# open-circuit.net
KiCad netlist of a schematic drawn in EAGLE
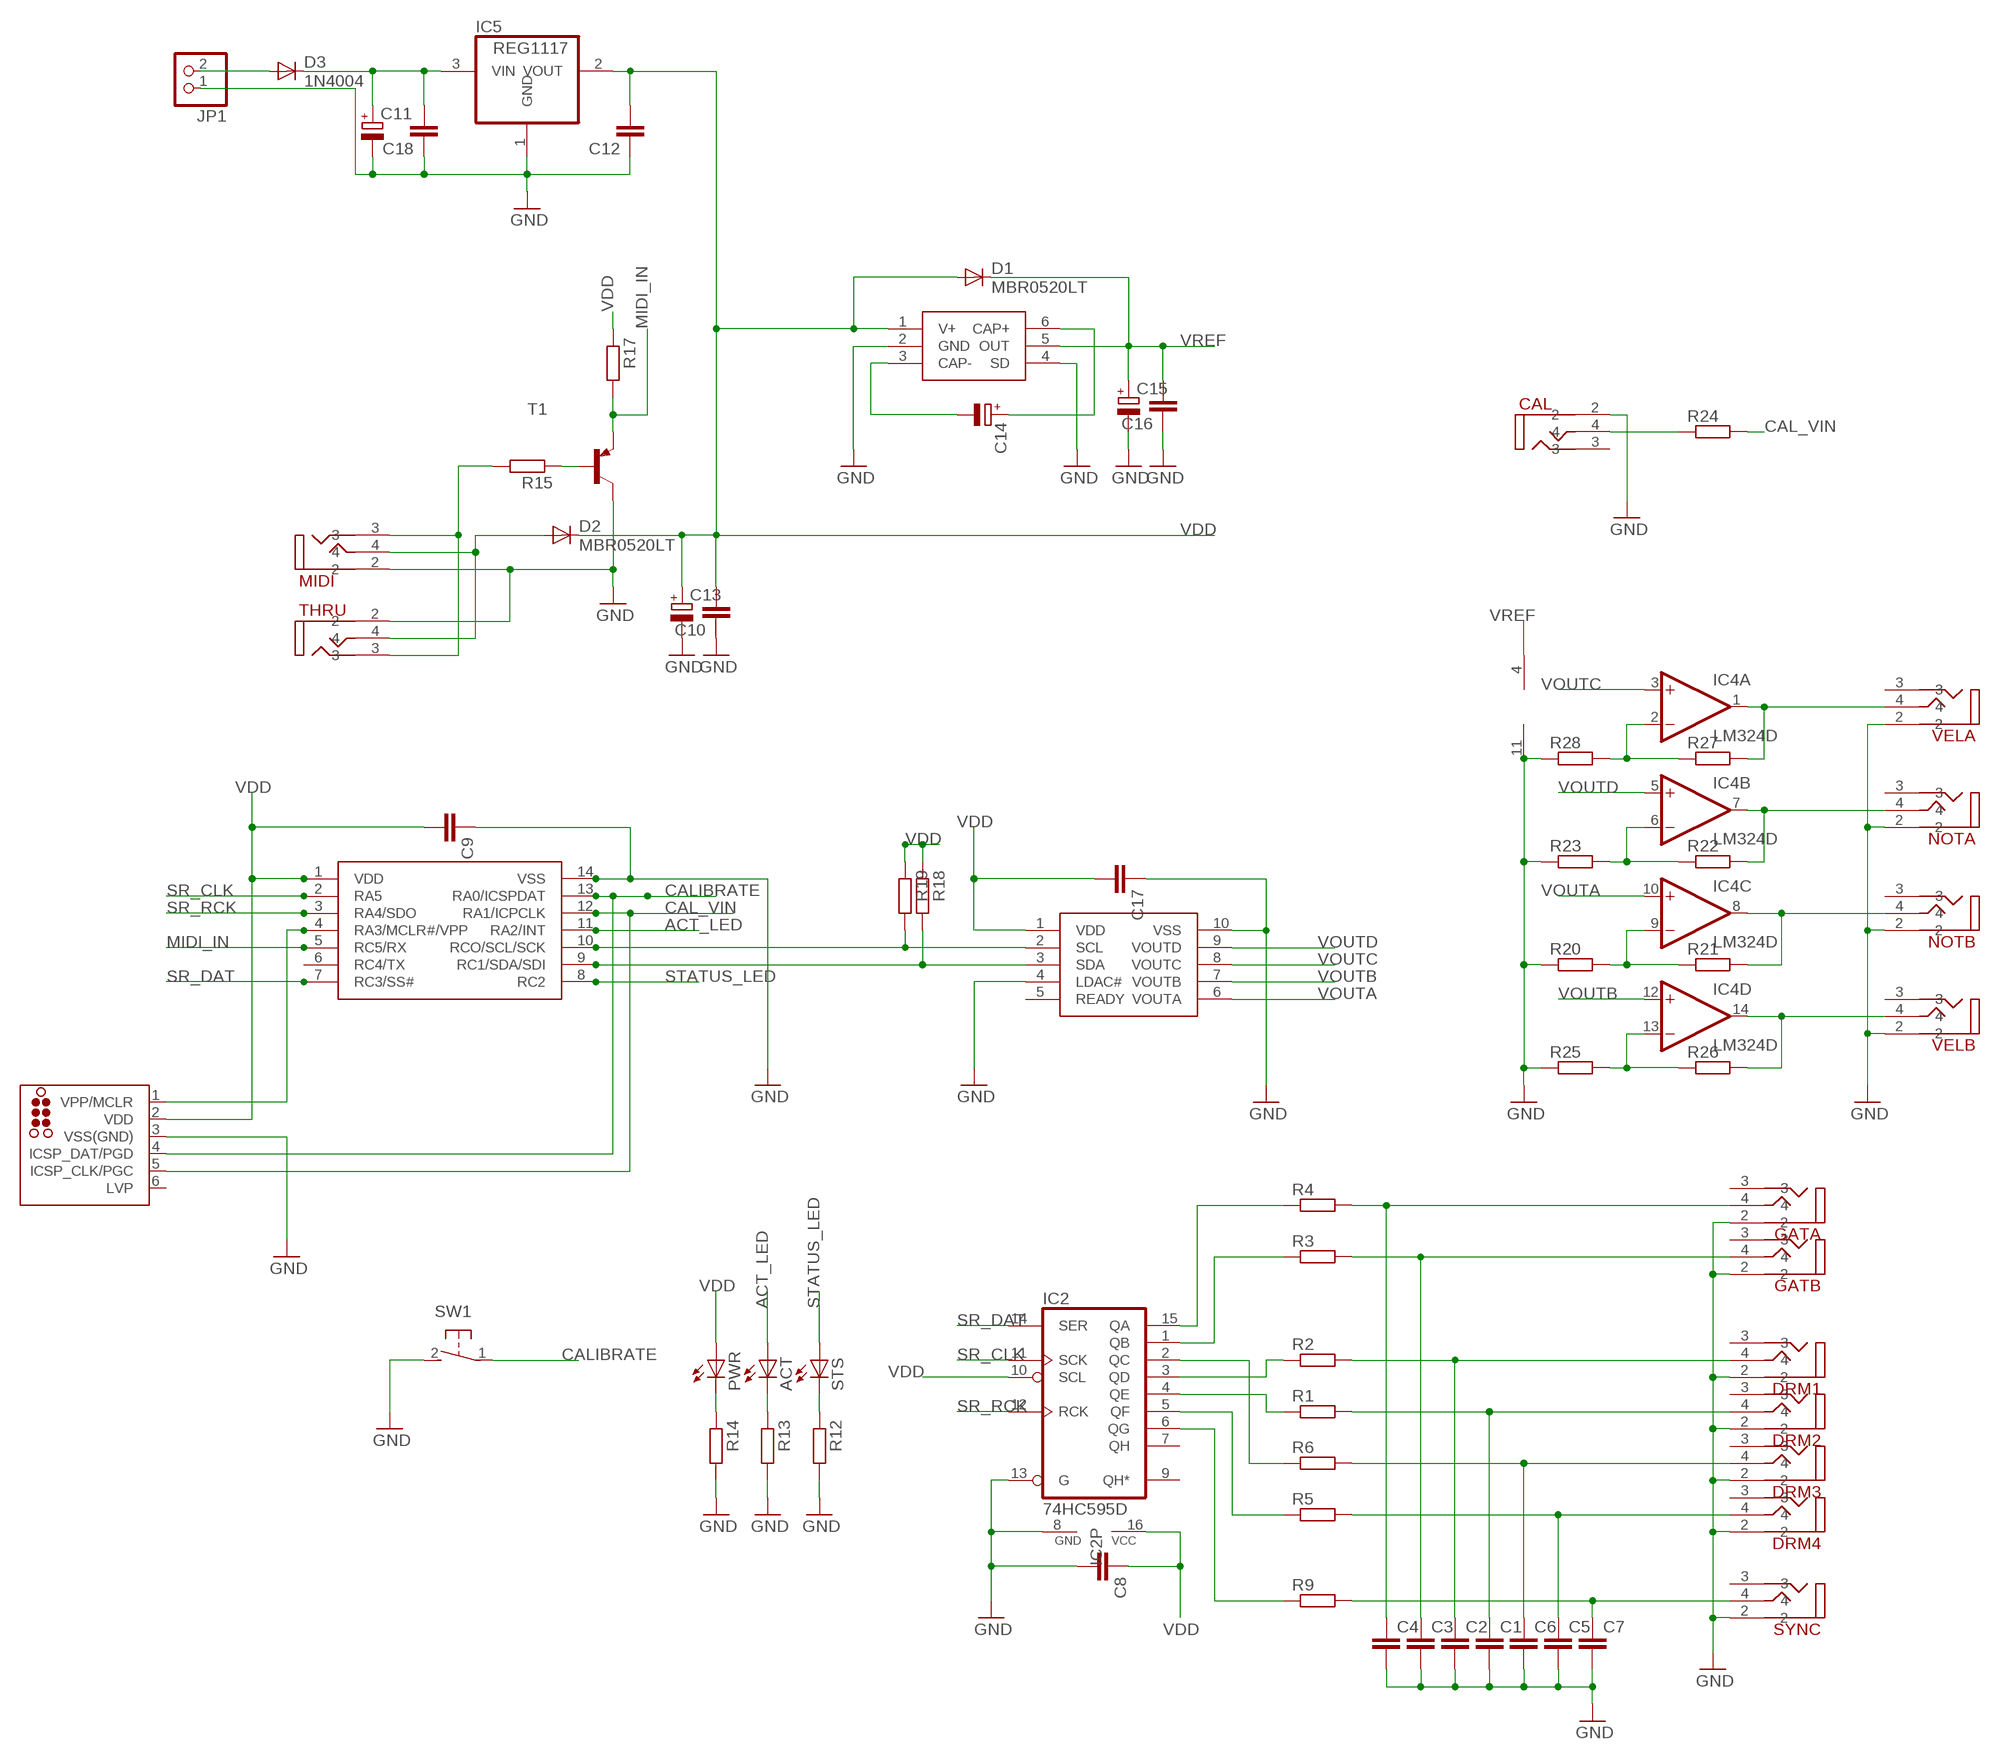
[diagram p0: schematic, sheet 1]

(export (version "E")
  (design (tool "Eeschema 10.0.6"))
  (components
    (comp (ref "ACT")
      (value "LED3MM")
      (footprint "eagle-import:LED3MM")
      (libsource (lib "eagle-import") (part "LED3MM"))
    )
    (comp (ref "C1")
      (value "C-EUC0805")
      (footprint "eagle-import:C0805")
      (libsource (lib "eagle-import") (part "C-EUC0805"))
    )
    (comp (ref "C2")
      (value "C-EUC0805")
      (footprint "eagle-import:C0805")
      (libsource (lib "eagle-import") (part "C-EUC0805"))
    )
    (comp (ref "C3")
      (value "C-EUC0805")
      (footprint "eagle-import:C0805")
      (libsource (lib "eagle-import") (part "C-EUC0805"))
    )
    (comp (ref "C4")
      (value "C-EUC0805")
      (footprint "eagle-import:C0805")
      (libsource (lib "eagle-import") (part "C-EUC0805"))
    )
    (comp (ref "C5")
      (value "C-EUC0805")
      (footprint "eagle-import:C0805")
      (libsource (lib "eagle-import") (part "C-EUC0805"))
    )
    (comp (ref "C6")
      (value "C-EUC0805")
      (footprint "eagle-import:C0805")
      (libsource (lib "eagle-import") (part "C-EUC0805"))
    )
    (comp (ref "C7")
      (value "C-EUC0805")
      (footprint "eagle-import:C0805")
      (libsource (lib "eagle-import") (part "C-EUC0805"))
    )
    (comp (ref "C8")
      (value "C-EUC0805")
      (footprint "eagle-import:C0805")
      (libsource (lib "eagle-import") (part "C-EUC0805"))
    )
    (comp (ref "C9")
      (value "C-EUC0805")
      (footprint "eagle-import:C0805")
      (libsource (lib "eagle-import") (part "C-EUC0805"))
    )
    (comp (ref "C10")
      (value "C-EUC0805")
      (footprint "eagle-import:C0805")
      (libsource (lib "eagle-import") (part "C-EUC0805"))
    )
    (comp (ref "C11")
      (value "CPOL-EUE2.5-5")
      (footprint "eagle-import:E2,5-5")
      (libsource (lib "eagle-import") (part "resistor_CPOL-EUE2.5-5"))
    )
    (comp (ref "C12")
      (value "C-EUC0805")
      (footprint "eagle-import:C0805")
      (libsource (lib "eagle-import") (part "C-EUC0805"))
    )
    (comp (ref "C13")
      (value "CPOL-EUSMCA")
      (footprint "eagle-import:SMC_A")
      (libsource (lib "eagle-import") (part "CPOL-EUSMCA"))
    )
    (comp (ref "C14")
      (value "CPOL-EUSMCA")
      (footprint "eagle-import:SMC_A")
      (libsource (lib "eagle-import") (part "CPOL-EUSMCA"))
    )
    (comp (ref "C15")
      (value "CPOL-EUSMCA")
      (footprint "eagle-import:SMC_A")
      (libsource (lib "eagle-import") (part "CPOL-EUSMCA"))
    )
    (comp (ref "C16")
      (value "C-EUC0805")
      (footprint "eagle-import:C0805")
      (libsource (lib "eagle-import") (part "C-EUC0805"))
    )
    (comp (ref "C17")
      (value "C-EUC0805")
      (footprint "eagle-import:C0805")
      (libsource (lib "eagle-import") (part "C-EUC0805"))
    )
    (comp (ref "C18")
      (value "C-EUC0805")
      (footprint "eagle-import:C0805")
      (libsource (lib "eagle-import") (part "C-EUC0805"))
    )
    (comp (ref "CAL")
      (value "VERTICAL_3_5MM_SOCKET")
      (footprint "eagle-import:VERTICAL_3_5MM_SOCKET")
      (libsource (lib "eagle-import") (part "VERTICAL_3_5MM_SOCKET"))
    )
    (comp (ref "D1")
      (value "MBR0520LT")
      (footprint "eagle-import:SOD123")
      (libsource (lib "eagle-import") (part "MBR0520LT"))
    )
    (comp (ref "D2")
      (value "MBR0520LT")
      (footprint "eagle-import:SOD123")
      (libsource (lib "eagle-import") (part "MBR0520LT"))
    )
    (comp (ref "D3")
      (value "1N4004")
      (footprint "eagle-import:DO-VERT")
      (libsource (lib "eagle-import") (part "1N4004"))
    )
    (comp (ref "DRM1")
      (value "VERTICAL_3_5MM_SOCKET")
      (footprint "eagle-import:VERTICAL_3_5MM_SOCKET")
      (libsource (lib "eagle-import") (part "VERTICAL_3_5MM_SOCKET"))
    )
    (comp (ref "DRM2")
      (value "VERTICAL_3_5MM_SOCKET")
      (footprint "eagle-import:VERTICAL_3_5MM_SOCKET")
      (libsource (lib "eagle-import") (part "VERTICAL_3_5MM_SOCKET"))
    )
    (comp (ref "DRM3")
      (value "VERTICAL_3_5MM_SOCKET")
      (footprint "eagle-import:VERTICAL_3_5MM_SOCKET")
      (libsource (lib "eagle-import") (part "VERTICAL_3_5MM_SOCKET"))
    )
    (comp (ref "DRM4")
      (value "VERTICAL_3_5MM_SOCKET")
      (footprint "eagle-import:VERTICAL_3_5MM_SOCKET")
      (libsource (lib "eagle-import") (part "VERTICAL_3_5MM_SOCKET"))
    )
    (comp (ref "GATA")
      (value "VERTICAL_3_5MM_SOCKET")
      (footprint "eagle-import:VERTICAL_3_5MM_SOCKET")
      (libsource (lib "eagle-import") (part "VERTICAL_3_5MM_SOCKET"))
    )
    (comp (ref "GATB")
      (value "VERTICAL_3_5MM_SOCKET")
      (footprint "eagle-import:VERTICAL_3_5MM_SOCKET")
      (libsource (lib "eagle-import") (part "VERTICAL_3_5MM_SOCKET"))
    )
    (comp (ref "IC1")
      (value "PIC16F1825SO14")
      (footprint "eagle-import:SO14")
      (libsource (lib "eagle-import") (part "PIC16F1825SO14"))
    )
    (comp (ref "IC2")
      (value "74HC595D")
      (footprint "eagle-import:SO16")
      (libsource (lib "eagle-import") (part "74595DHC"))
    )
    (comp (ref "IC3")
      (value "MCP4728_QUAD_DAC")
      (footprint "eagle-import:MSOP10")
      (libsource (lib "eagle-import") (part "MCP4728_QUAD_DAC"))
    )
    (comp (ref "IC4")
      (value "LM324D")
      (footprint "eagle-import:SO14")
      (libsource (lib "eagle-import") (part "LM324D"))
    )
    (comp (ref "IC5")
      (value "REG1117")
      (footprint "eagle-import:SOT223")
      (libsource (lib "eagle-import") (part "REG1117"))
    )
    (comp (ref "IC6")
      (value "LM27675M5_CHARGEPUMP")
      (footprint "eagle-import:SOT23-6")
      (libsource (lib "eagle-import") (part "LM27675M5_CHARGEPUMP"))
    )
    (comp (ref "ISCP")
      (value "TC2030-MCP-NL")
      (footprint "eagle-import:TC2030-MCP-NL")
      (libsource (lib "eagle-import") (part "TC2030-MCP-NL"))
    )
    (comp (ref "JP1")
      (value "PINHD-1X2")
      (footprint "eagle-import:1X02")
      (libsource (lib "eagle-import") (part "PINHD-1X2"))
    )
    (comp (ref "MIDI")
      (value "VERTICAL_3_5MM_SOCKET")
      (footprint "eagle-import:VERTICAL_3_5MM_SOCKET")
      (libsource (lib "eagle-import") (part "VERTICAL_3_5MM_SOCKET"))
    )
    (comp (ref "NOTA")
      (value "VERTICAL_3_5MM_SOCKET")
      (footprint "eagle-import:VERTICAL_3_5MM_SOCKET")
      (libsource (lib "eagle-import") (part "VERTICAL_3_5MM_SOCKET"))
    )
    (comp (ref "NOTB")
      (value "VERTICAL_3_5MM_SOCKET")
      (footprint "eagle-import:VERTICAL_3_5MM_SOCKET")
      (libsource (lib "eagle-import") (part "VERTICAL_3_5MM_SOCKET"))
    )
    (comp (ref "PWR")
      (value "LED3MM")
      (footprint "eagle-import:LED3MM")
      (libsource (lib "eagle-import") (part "LED3MM"))
    )
    (comp (ref "R1")
      (value "R-EU_R0805")
      (footprint "eagle-import:R0805")
      (libsource (lib "eagle-import") (part "R-EU_R0805"))
    )
    (comp (ref "R2")
      (value "R-EU_R0805")
      (footprint "eagle-import:R0805")
      (libsource (lib "eagle-import") (part "R-EU_R0805"))
    )
    (comp (ref "R3")
      (value "R-EU_R0805")
      (footprint "eagle-import:R0805")
      (libsource (lib "eagle-import") (part "R-EU_R0805"))
    )
    (comp (ref "R4")
      (value "R-EU_R0805")
      (footprint "eagle-import:R0805")
      (libsource (lib "eagle-import") (part "R-EU_R0805"))
    )
    (comp (ref "R5")
      (value "R-EU_R0805")
      (footprint "eagle-import:R0805")
      (libsource (lib "eagle-import") (part "R-EU_R0805"))
    )
    (comp (ref "R6")
      (value "R-EU_R0805")
      (footprint "eagle-import:R0805")
      (libsource (lib "eagle-import") (part "R-EU_R0805"))
    )
    (comp (ref "R9")
      (value "R-EU_R0805")
      (footprint "eagle-import:R0805")
      (libsource (lib "eagle-import") (part "R-EU_R0805"))
    )
    (comp (ref "R12")
      (value "R-EU_R0805")
      (footprint "eagle-import:R0805")
      (libsource (lib "eagle-import") (part "R-EU_R0805"))
    )
    (comp (ref "R13")
      (value "R-EU_R0805")
      (footprint "eagle-import:R0805")
      (libsource (lib "eagle-import") (part "R-EU_R0805"))
    )
    (comp (ref "R14")
      (value "R-EU_R0805")
      (footprint "eagle-import:R0805")
      (libsource (lib "eagle-import") (part "R-EU_R0805"))
    )
    (comp (ref "R15")
      (value "R-EU_R0805")
      (footprint "eagle-import:R0805")
      (libsource (lib "eagle-import") (part "R-EU_R0805"))
    )
    (comp (ref "R17")
      (value "R-EU_R0805")
      (footprint "eagle-import:R0805")
      (libsource (lib "eagle-import") (part "R-EU_R0805"))
    )
    (comp (ref "R18")
      (value "R-EU_R0805")
      (footprint "eagle-import:R0805")
      (libsource (lib "eagle-import") (part "R-EU_R0805"))
    )
    (comp (ref "R19")
      (value "R-EU_R0805")
      (footprint "eagle-import:R0805")
      (libsource (lib "eagle-import") (part "R-EU_R0805"))
    )
    (comp (ref "R20")
      (value "R-EU_R0805")
      (footprint "eagle-import:R0805")
      (libsource (lib "eagle-import") (part "R-EU_R0805"))
    )
    (comp (ref "R21")
      (value "R-EU_R0805")
      (footprint "eagle-import:R0805")
      (libsource (lib "eagle-import") (part "R-EU_R0805"))
    )
    (comp (ref "R22")
      (value "R-EU_R0805")
      (footprint "eagle-import:R0805")
      (libsource (lib "eagle-import") (part "R-EU_R0805"))
    )
    (comp (ref "R23")
      (value "R-EU_R0805")
      (footprint "eagle-import:R0805")
      (libsource (lib "eagle-import") (part "R-EU_R0805"))
    )
    (comp (ref "R24")
      (value "R-EU_R0805")
      (footprint "eagle-import:R0805")
      (libsource (lib "eagle-import") (part "R-EU_R0805"))
    )
    (comp (ref "R25")
      (value "R-EU_R0805")
      (footprint "eagle-import:R0805")
      (libsource (lib "eagle-import") (part "R-EU_R0805"))
    )
    (comp (ref "R26")
      (value "R-EU_R0805")
      (footprint "eagle-import:R0805")
      (libsource (lib "eagle-import") (part "R-EU_R0805"))
    )
    (comp (ref "R27")
      (value "R-EU_R0805")
      (footprint "eagle-import:R0805")
      (libsource (lib "eagle-import") (part "R-EU_R0805"))
    )
    (comp (ref "R28")
      (value "R-EU_R0805")
      (footprint "eagle-import:R0805")
      (libsource (lib "eagle-import") (part "R-EU_R0805"))
    )
    (comp (ref "STS")
      (value "LED3MM")
      (footprint "eagle-import:LED3MM")
      (libsource (lib "eagle-import") (part "LED3MM"))
    )
    (comp (ref "SW1")
      (value "31-XX")
      (footprint "eagle-import:B3F-31XX")
      (fields (field (name "MPN") "B3F-3100"))
      (libsource (lib "eagle-import") (part "31-XX"))
    )
    (comp (ref "SYNC")
      (value "VERTICAL_3_5MM_SOCKET")
      (footprint "eagle-import:VERTICAL_3_5MM_SOCKET")
      (libsource (lib "eagle-import") (part "VERTICAL_3_5MM_SOCKET"))
    )
    (comp (ref "T1")
      (value "MMBT3906LT1-PNP-SOT23-BEC")
      (footprint "eagle-import:SOT23-BEC")
      (libsource (lib "eagle-import") (part "-PNP-SOT23-BECMMBT3906LT1"))
    )
    (comp (ref "THRU")
      (value "VERTICAL_3_5MM_SOCKET")
      (footprint "eagle-import:VERTICAL_3_5MM_SOCKET")
      (libsource (lib "eagle-import") (part "VERTICAL_3_5MM_SOCKET"))
    )
    (comp (ref "VELA")
      (value "VERTICAL_3_5MM_SOCKET")
      (footprint "eagle-import:VERTICAL_3_5MM_SOCKET")
      (libsource (lib "eagle-import") (part "VERTICAL_3_5MM_SOCKET"))
    )
    (comp (ref "VELB")
      (value "VERTICAL_3_5MM_SOCKET")
      (footprint "eagle-import:VERTICAL_3_5MM_SOCKET")
      (libsource (lib "eagle-import") (part "VERTICAL_3_5MM_SOCKET"))
    )
  )
  (nets
    (net (code "1") (name "/ACT_LED") (class "Default")
      (node (ref "ACT") (pin "A") (pinfunction "A_A") (pintype "passive"))
      (node (ref "IC1") (pin "11") (pinfunction "RA2/INT_11") (pintype "bidirectional"))
    )
    (net (code "2") (name "/CALIBRATE") (class "Default")
      (node (ref "IC1") (pin "13") (pinfunction "RA0/ICSPDAT_13") (pintype "bidirectional"))
      (node (ref "ISCP") (pin "4") (pinfunction "ICSP_DAT/PGD_4") (pintype "bidirectional"))
      (node (ref "SW1") (pin "1") (pinfunction "P_1") (pintype "passive"))
    )
    (net (code "3") (name "/CAL_VIN") (class "Default")
      (node (ref "IC1") (pin "12") (pinfunction "RA1/ICPCLK_12") (pintype "bidirectional"))
      (node (ref "ISCP") (pin "5") (pinfunction "ICSP_CLK/PGC_5") (pintype "output"))
      (node (ref "R24") (pin "2") (pinfunction "2_2") (pintype "passive"))
    )
    (net (code "4") (name "/MIDI_IN") (class "Default")
      (node (ref "IC1") (pin "5") (pinfunction "RC5/RX_5") (pintype "bidirectional"))
      (node (ref "R17") (pin "2") (pinfunction "2_2") (pintype "passive"))
      (node (ref "T1") (pin "E") (pinfunction "E_E") (pintype "passive"))
    )
    (net (code "5") (name "/SR_CLK") (class "Default")
      (node (ref "IC1") (pin "2") (pinfunction "RA5_2") (pintype "bidirectional"))
      (node (ref "IC2") (pin "11") (pinfunction "SCK_11") (pintype "input"))
    )
    (net (code "6") (name "/SR_DAT") (class "Default")
      (node (ref "IC1") (pin "7") (pinfunction "RC3/SS#_7") (pintype "bidirectional"))
      (node (ref "IC2") (pin "14") (pinfunction "SER_14") (pintype "input"))
    )
    (net (code "7") (name "/SR_RCK") (class "Default")
      (node (ref "IC1") (pin "3") (pinfunction "RA4/SDO_3") (pintype "bidirectional"))
      (node (ref "IC2") (pin "12") (pinfunction "RCK_12") (pintype "input"))
    )
    (net (code "8") (name "/STATUS_LED") (class "Default")
      (node (ref "IC1") (pin "8") (pinfunction "RC2_8") (pintype "bidirectional"))
      (node (ref "STS") (pin "A") (pinfunction "A_A") (pintype "passive"))
    )
    (net (code "9") (name "/VDD") (class "Default")
      (node (ref "C10") (pin "2") (pinfunction "2_2") (pintype "passive"))
      (node (ref "C12") (pin "2") (pinfunction "2_2") (pintype "passive"))
      (node (ref "C13") (pin "+") (pinfunction "+_+") (pintype "passive"))
      (node (ref "C17") (pin "2") (pinfunction "2_2") (pintype "passive"))
      (node (ref "C8") (pin "1") (pinfunction "1_1") (pintype "passive"))
      (node (ref "C9") (pin "2") (pinfunction "2_2") (pintype "passive"))
      (node (ref "D1") (pin "A") (pinfunction "A_A") (pintype "passive"))
      (node (ref "D2") (pin "C") (pinfunction "C_C") (pintype "passive"))
      (node (ref "IC1") (pin "1") (pinfunction "VDD_1") (pintype "power_in"))
      (node (ref "IC2") (pin "10") (pinfunction "SCL_10") (pintype "input"))
      (node (ref "IC2") (pin "16") (pinfunction "VCC_16") (pintype "power_in"))
      (node (ref "IC3") (pin "1") (pinfunction "VDD_1") (pintype "power_in"))
      (node (ref "IC5") (pin "2") (pinfunction "VOUT_2") (pintype "output"))
      (node (ref "IC6") (pin "1") (pinfunction "V+_1") (pintype "bidirectional"))
      (node (ref "ISCP") (pin "2") (pinfunction "VDD_2") (pintype "power_in"))
      (node (ref "PWR") (pin "A") (pinfunction "A_A") (pintype "passive"))
      (node (ref "R17") (pin "1") (pinfunction "1_1") (pintype "passive"))
      (node (ref "R18") (pin "1") (pinfunction "1_1") (pintype "passive"))
      (node (ref "R19") (pin "1") (pinfunction "1_1") (pintype "passive"))
    )
    (net (code "10") (name "/VOUTA") (class "Default")
      (node (ref "IC3") (pin "6") (pinfunction "VOUTA_6") (pintype "bidirectional"))
      (node (ref "IC4") (pin "10") (pinfunction "+IN_10") (pintype "input"))
    )
    (net (code "11") (name "/VOUTB") (class "Default")
      (node (ref "IC3") (pin "7") (pinfunction "VOUTB_7") (pintype "bidirectional"))
      (node (ref "IC4") (pin "12") (pinfunction "+IN_12") (pintype "input"))
    )
    (net (code "12") (name "/VOUTC") (class "Default")
      (node (ref "IC3") (pin "8") (pinfunction "VOUTC_8") (pintype "bidirectional"))
      (node (ref "IC4") (pin "3") (pinfunction "+IN_3") (pintype "input"))
    )
    (net (code "13") (name "/VOUTD") (class "Default")
      (node (ref "IC3") (pin "9") (pinfunction "VOUTD_9") (pintype "bidirectional"))
      (node (ref "IC4") (pin "5") (pinfunction "+IN_5") (pintype "input"))
    )
    (net (code "14") (name "/VREF") (class "Default")
      (node (ref "C15") (pin "+") (pinfunction "+_+") (pintype "passive"))
      (node (ref "C16") (pin "2") (pinfunction "2_2") (pintype "passive"))
      (node (ref "D1") (pin "C") (pinfunction "C_C") (pintype "passive"))
      (node (ref "IC4") (pin "4") (pinfunction "V+_4") (pintype "power_in"))
      (node (ref "IC6") (pin "5") (pinfunction "OUT_5") (pintype "bidirectional"))
    )
    (net (code "15") (name "GND") (class "Default")
      (node (ref "C1") (pin "2") (pinfunction "2_2") (pintype "passive"))
      (node (ref "C10") (pin "1") (pinfunction "1_1") (pintype "passive"))
      (node (ref "C11") (pin "-") (pinfunction "-_-") (pintype "passive"))
      (node (ref "C12") (pin "1") (pinfunction "1_1") (pintype "passive"))
      (node (ref "C13") (pin "-") (pinfunction "-_-") (pintype "passive"))
      (node (ref "C15") (pin "-") (pinfunction "-_-") (pintype "passive"))
      (node (ref "C16") (pin "1") (pinfunction "1_1") (pintype "passive"))
      (node (ref "C17") (pin "1") (pinfunction "1_1") (pintype "passive"))
      (node (ref "C18") (pin "1") (pinfunction "1_1") (pintype "passive"))
      (node (ref "C2") (pin "2") (pinfunction "2_2") (pintype "passive"))
      (node (ref "C3") (pin "2") (pinfunction "2_2") (pintype "passive"))
      (node (ref "C4") (pin "2") (pinfunction "2_2") (pintype "passive"))
      (node (ref "C5") (pin "2") (pinfunction "2_2") (pintype "passive"))
      (node (ref "C6") (pin "2") (pinfunction "2_2") (pintype "passive"))
      (node (ref "C7") (pin "2") (pinfunction "2_2") (pintype "passive"))
      (node (ref "C8") (pin "2") (pinfunction "2_2") (pintype "passive"))
      (node (ref "C9") (pin "1") (pinfunction "1_1") (pintype "passive"))
      (node (ref "CAL") (pin "2") (pinfunction "2_2") (pintype "bidirectional"))
      (node (ref "DRM1") (pin "2") (pinfunction "2_2") (pintype "bidirectional"))
      (node (ref "DRM2") (pin "2") (pinfunction "2_2") (pintype "bidirectional"))
      (node (ref "DRM3") (pin "2") (pinfunction "2_2") (pintype "bidirectional"))
      (node (ref "DRM4") (pin "2") (pinfunction "2_2") (pintype "bidirectional"))
      (node (ref "GATA") (pin "2") (pinfunction "2_2") (pintype "bidirectional"))
      (node (ref "GATB") (pin "2") (pinfunction "2_2") (pintype "bidirectional"))
      (node (ref "IC1") (pin "14") (pinfunction "VSS_14") (pintype "power_in"))
      (node (ref "IC2") (pin "13") (pinfunction "G_13") (pintype "input"))
      (node (ref "IC2") (pin "8") (pinfunction "GND_8") (pintype "power_in"))
      (node (ref "IC3") (pin "10") (pinfunction "VSS_10") (pintype "power_in"))
      (node (ref "IC3") (pin "4") (pinfunction "LDAC#_4") (pintype "bidirectional"))
      (node (ref "IC4") (pin "11") (pinfunction "V-_11") (pintype "power_in"))
      (node (ref "IC5") (pin "1") (pinfunction "GND_1") (pintype "power_in"))
      (node (ref "IC6") (pin "2") (pinfunction "GND_2") (pintype "bidirectional"))
      (node (ref "IC6") (pin "4") (pinfunction "SD_4") (pintype "bidirectional"))
      (node (ref "ISCP") (pin "3") (pinfunction "VSS(GND)_3") (pintype "power_in"))
      (node (ref "JP1") (pin "1") (pinfunction "1_1") (pintype "passive"))
      (node (ref "MIDI") (pin "2") (pinfunction "2_2") (pintype "bidirectional"))
      (node (ref "NOTA") (pin "2") (pinfunction "2_2") (pintype "bidirectional"))
      (node (ref "NOTB") (pin "2") (pinfunction "2_2") (pintype "bidirectional"))
      (node (ref "R12") (pin "2") (pinfunction "2_2") (pintype "passive"))
      (node (ref "R13") (pin "2") (pinfunction "2_2") (pintype "passive"))
      (node (ref "R14") (pin "2") (pinfunction "2_2") (pintype "passive"))
      (node (ref "R20") (pin "1") (pinfunction "1_1") (pintype "passive"))
      (node (ref "R23") (pin "1") (pinfunction "1_1") (pintype "passive"))
      (node (ref "R25") (pin "1") (pinfunction "1_1") (pintype "passive"))
      (node (ref "R28") (pin "1") (pinfunction "1_1") (pintype "passive"))
      (node (ref "SW1") (pin "2") (pinfunction "S_2") (pintype "passive"))
      (node (ref "SYNC") (pin "2") (pinfunction "2_2") (pintype "bidirectional"))
      (node (ref "T1") (pin "C") (pinfunction "C_C") (pintype "passive"))
      (node (ref "THRU") (pin "2") (pinfunction "2_2") (pintype "bidirectional"))
      (node (ref "VELA") (pin "2") (pinfunction "2_2") (pintype "bidirectional"))
      (node (ref "VELB") (pin "2") (pinfunction "2_2") (pintype "bidirectional"))
    )
    (net (code "16") (name "Net-(ACT-C)") (class "Default")
      (node (ref "ACT") (pin "K") (pinfunction "C_K") (pintype "passive"))
      (node (ref "R13") (pin "1") (pinfunction "1_1") (pintype "passive"))
    )
    (net (code "17") (name "Net-(C1-Pad1)") (class "Default")
      (node (ref "C1") (pin "1") (pinfunction "1_1") (pintype "passive"))
      (node (ref "DRM2") (pin "4") (pinfunction "4_4") (pintype "bidirectional"))
      (node (ref "R1") (pin "2") (pinfunction "2_2") (pintype "passive"))
    )
    (net (code "18") (name "Net-(C2-Pad1)") (class "Default")
      (node (ref "C2") (pin "1") (pinfunction "1_1") (pintype "passive"))
      (node (ref "DRM1") (pin "4") (pinfunction "4_4") (pintype "bidirectional"))
      (node (ref "R2") (pin "2") (pinfunction "2_2") (pintype "passive"))
    )
    (net (code "19") (name "Net-(C3-Pad1)") (class "Default")
      (node (ref "C3") (pin "1") (pinfunction "1_1") (pintype "passive"))
      (node (ref "GATB") (pin "4") (pinfunction "4_4") (pintype "bidirectional"))
      (node (ref "R3") (pin "2") (pinfunction "2_2") (pintype "passive"))
    )
    (net (code "20") (name "Net-(C4-Pad1)") (class "Default")
      (node (ref "C4") (pin "1") (pinfunction "1_1") (pintype "passive"))
      (node (ref "GATA") (pin "4") (pinfunction "4_4") (pintype "bidirectional"))
      (node (ref "R4") (pin "2") (pinfunction "2_2") (pintype "passive"))
    )
    (net (code "21") (name "Net-(C5-Pad1)") (class "Default")
      (node (ref "C5") (pin "1") (pinfunction "1_1") (pintype "passive"))
      (node (ref "DRM4") (pin "4") (pinfunction "4_4") (pintype "bidirectional"))
      (node (ref "R5") (pin "2") (pinfunction "2_2") (pintype "passive"))
    )
    (net (code "22") (name "Net-(C6-Pad1)") (class "Default")
      (node (ref "C6") (pin "1") (pinfunction "1_1") (pintype "passive"))
      (node (ref "DRM3") (pin "4") (pinfunction "4_4") (pintype "bidirectional"))
      (node (ref "R6") (pin "2") (pinfunction "2_2") (pintype "passive"))
    )
    (net (code "23") (name "Net-(C7-Pad1)") (class "Default")
      (node (ref "C7") (pin "1") (pinfunction "1_1") (pintype "passive"))
      (node (ref "R9") (pin "2") (pinfunction "2_2") (pintype "passive"))
      (node (ref "SYNC") (pin "4") (pinfunction "4_4") (pintype "bidirectional"))
    )
    (net (code "24") (name "Net-(CAL-Pad4)") (class "Default")
      (node (ref "CAL") (pin "4") (pinfunction "4_4") (pintype "bidirectional"))
      (node (ref "R24") (pin "1") (pinfunction "1_1") (pintype "passive"))
    )
    (net (code "25") (name "Net-(D2-PadA)") (class "Default")
      (node (ref "D2") (pin "A") (pinfunction "A_A") (pintype "passive"))
      (node (ref "MIDI") (pin "4") (pinfunction "4_4") (pintype "bidirectional"))
      (node (ref "THRU") (pin "4") (pinfunction "4_4") (pintype "bidirectional"))
    )
    (net (code "26") (name "Net-(D3-PadA)") (class "Default")
      (node (ref "D3") (pin "A") (pinfunction "A_A") (pintype "passive"))
      (node (ref "JP1") (pin "2") (pinfunction "2_2") (pintype "passive"))
    )
    (net (code "27") (name "Net-(IC1-RA3{slash}MCLR#{slash}VPP)") (class "Default")
      (node (ref "IC1") (pin "4") (pinfunction "RA3/MCLR#/VPP_4") (pintype "input"))
      (node (ref "ISCP") (pin "1") (pinfunction "VPP/MCLR_1") (pintype "passive"))
    )
    (net (code "28") (name "Net-(IC1-RC1{slash}SDA{slash}SDI)") (class "Default")
      (node (ref "IC1") (pin "9") (pinfunction "RC1/SDA/SDI_9") (pintype "bidirectional"))
      (node (ref "IC3") (pin "3") (pinfunction "SDA_3") (pintype "bidirectional"))
      (node (ref "R18") (pin "2") (pinfunction "2_2") (pintype "passive"))
    )
    (net (code "29") (name "Net-(IC1-RCO{slash}SCL{slash}SCK)") (class "Default")
      (node (ref "IC1") (pin "10") (pinfunction "RCO/SCL/SCK_10") (pintype "bidirectional"))
      (node (ref "IC3") (pin "2") (pinfunction "SCL_2") (pintype "bidirectional"))
      (node (ref "R19") (pin "2") (pinfunction "2_2") (pintype "passive"))
    )
    (net (code "30") (name "Net-(IC2A-QA)") (class "Default")
      (node (ref "IC2") (pin "15") (pinfunction "QA_15") (pintype "tri_state"))
      (node (ref "R4") (pin "1") (pinfunction "1_1") (pintype "passive"))
    )
    (net (code "31") (name "Net-(IC2A-QB)") (class "Default")
      (node (ref "IC2") (pin "1") (pinfunction "QB_1") (pintype "tri_state"))
      (node (ref "R3") (pin "1") (pinfunction "1_1") (pintype "passive"))
    )
    (net (code "32") (name "Net-(IC2A-QC)") (class "Default")
      (node (ref "IC2") (pin "2") (pinfunction "QC_2") (pintype "tri_state"))
      (node (ref "R6") (pin "1") (pinfunction "1_1") (pintype "passive"))
    )
    (net (code "33") (name "Net-(IC2A-QD)") (class "Default")
      (node (ref "IC2") (pin "3") (pinfunction "QD_3") (pintype "tri_state"))
      (node (ref "R2") (pin "1") (pinfunction "1_1") (pintype "passive"))
    )
    (net (code "34") (name "Net-(IC2A-QE)") (class "Default")
      (node (ref "IC2") (pin "4") (pinfunction "QE_4") (pintype "tri_state"))
      (node (ref "R1") (pin "1") (pinfunction "1_1") (pintype "passive"))
    )
    (net (code "35") (name "Net-(IC2A-QF)") (class "Default")
      (node (ref "IC2") (pin "5") (pinfunction "QF_5") (pintype "tri_state"))
      (node (ref "R5") (pin "1") (pinfunction "1_1") (pintype "passive"))
    )
    (net (code "36") (name "Net-(IC2A-QG)") (class "Default")
      (node (ref "IC2") (pin "6") (pinfunction "QG_6") (pintype "tri_state"))
      (node (ref "R9") (pin "1") (pinfunction "1_1") (pintype "passive"))
    )
    (net (code "37") (name "Net-(IC4A--IN)") (class "Default")
      (node (ref "IC4") (pin "2") (pinfunction "-IN_2") (pintype "input"))
      (node (ref "R27") (pin "1") (pinfunction "1_1") (pintype "passive"))
      (node (ref "R28") (pin "2") (pinfunction "2_2") (pintype "passive"))
    )
    (net (code "38") (name "Net-(IC4A-OUT)") (class "Default")
      (node (ref "IC4") (pin "1") (pinfunction "OUT_1") (pintype "output"))
      (node (ref "R27") (pin "2") (pinfunction "2_2") (pintype "passive"))
      (node (ref "VELA") (pin "4") (pinfunction "4_4") (pintype "bidirectional"))
    )
    (net (code "39") (name "Net-(IC4B--IN)") (class "Default")
      (node (ref "IC4") (pin "6") (pinfunction "-IN_6") (pintype "input"))
      (node (ref "R22") (pin "1") (pinfunction "1_1") (pintype "passive"))
      (node (ref "R23") (pin "2") (pinfunction "2_2") (pintype "passive"))
    )
    (net (code "40") (name "Net-(IC4B-OUT)") (class "Default")
      (node (ref "IC4") (pin "7") (pinfunction "OUT_7") (pintype "output"))
      (node (ref "NOTA") (pin "4") (pinfunction "4_4") (pintype "bidirectional"))
      (node (ref "R22") (pin "2") (pinfunction "2_2") (pintype "passive"))
    )
    (net (code "41") (name "Net-(IC4C--IN)") (class "Default")
      (node (ref "IC4") (pin "9") (pinfunction "-IN_9") (pintype "input"))
      (node (ref "R20") (pin "2") (pinfunction "2_2") (pintype "passive"))
      (node (ref "R21") (pin "1") (pinfunction "1_1") (pintype "passive"))
    )
    (net (code "42") (name "Net-(IC4C-OUT)") (class "Default")
      (node (ref "IC4") (pin "8") (pinfunction "OUT_8") (pintype "output"))
      (node (ref "NOTB") (pin "4") (pinfunction "4_4") (pintype "bidirectional"))
      (node (ref "R21") (pin "2") (pinfunction "2_2") (pintype "passive"))
    )
    (net (code "43") (name "Net-(IC4D--IN)") (class "Default")
      (node (ref "IC4") (pin "13") (pinfunction "-IN_13") (pintype "input"))
      (node (ref "R25") (pin "2") (pinfunction "2_2") (pintype "passive"))
      (node (ref "R26") (pin "1") (pinfunction "1_1") (pintype "passive"))
    )
    (net (code "44") (name "Net-(IC4D-OUT)") (class "Default")
      (node (ref "IC4") (pin "14") (pinfunction "OUT_14") (pintype "output"))
      (node (ref "R26") (pin "2") (pinfunction "2_2") (pintype "passive"))
      (node (ref "VELB") (pin "4") (pinfunction "4_4") (pintype "bidirectional"))
    )
    (net (code "45") (name "Net-(IC5-VIN)") (class "Default")
      (node (ref "C11") (pin "+") (pinfunction "+_+") (pintype "passive"))
      (node (ref "C18") (pin "2") (pinfunction "2_2") (pintype "passive"))
      (node (ref "D3") (pin "C") (pinfunction "C_C") (pintype "passive"))
      (node (ref "IC5") (pin "3") (pinfunction "VIN_3") (pintype "input"))
    )
    (net (code "46") (name "Net-(IC6-CAP+)") (class "Default")
      (node (ref "C14") (pin "+") (pinfunction "+_+") (pintype "passive"))
      (node (ref "IC6") (pin "6") (pinfunction "CAP+_6") (pintype "bidirectional"))
    )
    (net (code "47") (name "Net-(IC6-CAP-)") (class "Default")
      (node (ref "C14") (pin "-") (pinfunction "-_-") (pintype "passive"))
      (node (ref "IC6") (pin "3") (pinfunction "CAP-_3") (pintype "bidirectional"))
    )
    (net (code "48") (name "Net-(MIDI-Pad3)") (class "Default")
      (node (ref "MIDI") (pin "3") (pinfunction "3_3") (pintype "bidirectional"))
      (node (ref "R15") (pin "2") (pinfunction "2_2") (pintype "passive"))
      (node (ref "THRU") (pin "3") (pinfunction "3_3") (pintype "bidirectional"))
    )
    (net (code "49") (name "Net-(PWR-C)") (class "Default")
      (node (ref "PWR") (pin "K") (pinfunction "C_K") (pintype "passive"))
      (node (ref "R14") (pin "1") (pinfunction "1_1") (pintype "passive"))
    )
    (net (code "50") (name "Net-(R15-Pad1)") (class "Default")
      (node (ref "R15") (pin "1") (pinfunction "1_1") (pintype "passive"))
      (node (ref "T1") (pin "B") (pinfunction "B_B") (pintype "passive"))
    )
    (net (code "51") (name "Net-(STS-C)") (class "Default")
      (node (ref "R12") (pin "1") (pinfunction "1_1") (pintype "passive"))
      (node (ref "STS") (pin "K") (pinfunction "C_K") (pintype "passive"))
    )
    (net (code "52") (name "unconnected-(CAL-Pad3)") (class "Default")
      (node (ref "CAL") (pin "3") (pinfunction "3_3") (pintype "bidirectional"))
    )
    (net (code "53") (name "unconnected-(DRM1-Pad3)") (class "Default")
      (node (ref "DRM1") (pin "3") (pinfunction "3_3") (pintype "bidirectional"))
    )
    (net (code "54") (name "unconnected-(DRM2-Pad3)") (class "Default")
      (node (ref "DRM2") (pin "3") (pinfunction "3_3") (pintype "bidirectional"))
    )
    (net (code "55") (name "unconnected-(DRM3-Pad3)") (class "Default")
      (node (ref "DRM3") (pin "3") (pinfunction "3_3") (pintype "bidirectional"))
    )
    (net (code "56") (name "unconnected-(DRM4-Pad3)") (class "Default")
      (node (ref "DRM4") (pin "3") (pinfunction "3_3") (pintype "bidirectional"))
    )
    (net (code "57") (name "unconnected-(GATA-Pad3)") (class "Default")
      (node (ref "GATA") (pin "3") (pinfunction "3_3") (pintype "bidirectional"))
    )
    (net (code "58") (name "unconnected-(GATB-Pad3)") (class "Default")
      (node (ref "GATB") (pin "3") (pinfunction "3_3") (pintype "bidirectional"))
    )
    (net (code "59") (name "unconnected-(IC1-RC4{slash}TX-Pad6)") (class "Default")
      (node (ref "IC1") (pin "6") (pinfunction "RC4/TX_6") (pintype "bidirectional"))
    )
    (net (code "60") (name "unconnected-(IC2A-QH*-Pad9)") (class "Default")
      (node (ref "IC2") (pin "9") (pinfunction "QH*_9") (pintype "tri_state"))
    )
    (net (code "61") (name "unconnected-(IC2A-QH-Pad7)") (class "Default")
      (node (ref "IC2") (pin "7") (pinfunction "QH_7") (pintype "tri_state"))
    )
    (net (code "62") (name "unconnected-(IC3-READY-Pad5)") (class "Default")
      (node (ref "IC3") (pin "5") (pinfunction "READY_5") (pintype "bidirectional"))
    )
    (net (code "63") (name "unconnected-(ISCP-LVP-Pad6)") (class "Default")
      (node (ref "ISCP") (pin "6") (pinfunction "LVP_6") (pintype "bidirectional"))
    )
    (net (code "64") (name "unconnected-(NOTA-Pad3)") (class "Default")
      (node (ref "NOTA") (pin "3") (pinfunction "3_3") (pintype "bidirectional"))
    )
    (net (code "65") (name "unconnected-(NOTB-Pad3)") (class "Default")
      (node (ref "NOTB") (pin "3") (pinfunction "3_3") (pintype "bidirectional"))
    )
    (net (code "66") (name "unconnected-(SYNC-Pad3)") (class "Default")
      (node (ref "SYNC") (pin "3") (pinfunction "3_3") (pintype "bidirectional"))
    )
    (net (code "67") (name "unconnected-(VELA-Pad3)") (class "Default")
      (node (ref "VELA") (pin "3") (pinfunction "3_3") (pintype "bidirectional"))
    )
    (net (code "68") (name "unconnected-(VELB-Pad3)") (class "Default")
      (node (ref "VELB") (pin "3") (pinfunction "3_3") (pintype "bidirectional"))
    )
  )
)
